# 0_1.net
KiCad netlist of a schematic drawn in EAGLE
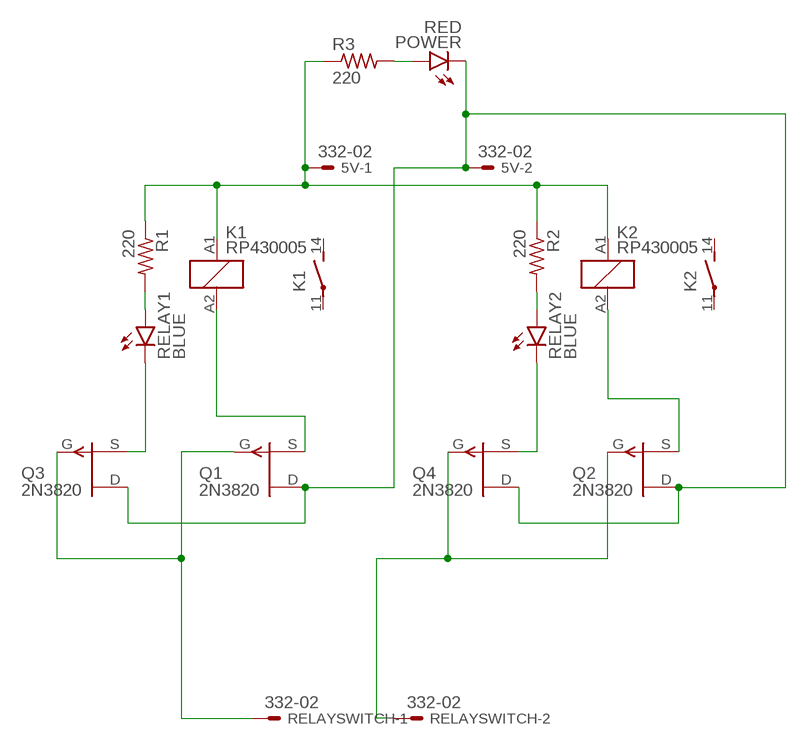
[diagram p0: schematic, sheet 1]

(export (version "E")
  (design (tool "Eeschema 10.0.6"))
  (components
    (comp (ref "5V")
      (value "332-02")
      (footprint "eagle-import:332-02")
      (libsource (lib "eagle-import") (part "332-02"))
    )
    (comp (ref "K1")
      (value "RP430005")
      (footprint "eagle-import:RT-N_O12A5")
      (libsource (lib "eagle-import") (part "RP?304005"))
    )
    (comp (ref "K2")
      (value "RP430005")
      (footprint "eagle-import:RT-N_O12A5")
      (libsource (lib "eagle-import") (part "RP?304005"))
    )
    (comp (ref "POWER")
      (value "RED")
      (footprint "eagle-import:LED5MM")
      (libsource (lib "eagle-import") (part "LED5MM"))
    )
    (comp (ref "Q1")
      (value "2N3820")
      (footprint "eagle-import:TO92")
      (libsource (lib "eagle-import") (part "2N3820"))
    )
    (comp (ref "Q2")
      (value "2N3820")
      (footprint "eagle-import:TO92")
      (libsource (lib "eagle-import") (part "2N3820"))
    )
    (comp (ref "Q3")
      (value "2N3820")
      (footprint "eagle-import:TO92")
      (libsource (lib "eagle-import") (part "2N3820"))
    )
    (comp (ref "Q4")
      (value "2N3820")
      (footprint "eagle-import:TO92")
      (libsource (lib "eagle-import") (part "2N3820"))
    )
    (comp (ref "R1")
      (value "220")
      (footprint "eagle-import:0204_7")
      (libsource (lib "eagle-import") (part "R-US_0204/7"))
    )
    (comp (ref "R2")
      (value "220")
      (footprint "eagle-import:0204_7")
      (libsource (lib "eagle-import") (part "R-US_0204/7"))
    )
    (comp (ref "R3")
      (value "220")
      (footprint "eagle-import:0204_7")
      (libsource (lib "eagle-import") (part "R-US_0204/7"))
    )
    (comp (ref "RELAY1")
      (value "BLUE")
      (footprint "eagle-import:LED5MM")
      (libsource (lib "eagle-import") (part "LED5MM"))
    )
    (comp (ref "RELAY2")
      (value "BLUE")
      (footprint "eagle-import:LED5MM")
      (libsource (lib "eagle-import") (part "LED5MM"))
    )
    (comp (ref "RELAYSWITCH")
      (value "332-02")
      (footprint "eagle-import:332-02")
      (libsource (lib "eagle-import") (part "332-02"))
    )
  )
  (nets
    (net (code "1") (name "Net-(5VA-S)") (class "Default")
      (node (ref "5V") (pin "1") (pinfunction "S_1") (pintype "passive"))
      (node (ref "K1") (pin "A1") (pinfunction "1_A1") (pintype "passive"))
      (node (ref "K2") (pin "A1") (pinfunction "1_A1") (pintype "passive"))
      (node (ref "R1") (pin "1") (pinfunction "1_1") (pintype "passive"))
      (node (ref "R2") (pin "1") (pinfunction "1_1") (pintype "passive"))
      (node (ref "R3") (pin "1") (pinfunction "1_1") (pintype "passive"))
    )
    (net (code "2") (name "Net-(5VB-S)") (class "Default")
      (node (ref "5V") (pin "2") (pinfunction "S_2") (pintype "passive"))
      (node (ref "POWER") (pin "K") (pinfunction "C_K") (pintype "passive"))
      (node (ref "Q1") (pin "3") (pinfunction "D_3") (pintype "passive"))
      (node (ref "Q2") (pin "3") (pinfunction "D_3") (pintype "passive"))
      (node (ref "Q3") (pin "3") (pinfunction "D_3") (pintype "passive"))
      (node (ref "Q4") (pin "3") (pinfunction "D_3") (pintype "passive"))
    )
    (net (code "3") (name "Net-(K1A-2)") (class "Default")
      (node (ref "K1") (pin "A2") (pinfunction "2_A2") (pintype "passive"))
      (node (ref "Q1") (pin "1") (pinfunction "S_1") (pintype "passive"))
    )
    (net (code "4") (name "Net-(K2A-2)") (class "Default")
      (node (ref "K2") (pin "A2") (pinfunction "2_A2") (pintype "passive"))
      (node (ref "Q2") (pin "1") (pinfunction "S_1") (pintype "passive"))
    )
    (net (code "5") (name "Net-(POWER-PadA)") (class "Default")
      (node (ref "POWER") (pin "A") (pinfunction "A_A") (pintype "passive"))
      (node (ref "R3") (pin "2") (pinfunction "2_2") (pintype "passive"))
    )
    (net (code "6") (name "Net-(Q1-G)") (class "Default")
      (node (ref "Q1") (pin "2") (pinfunction "G_2") (pintype "passive"))
      (node (ref "Q3") (pin "2") (pinfunction "G_2") (pintype "passive"))
      (node (ref "RELAYSWITCH") (pin "1") (pinfunction "S_1") (pintype "passive"))
    )
    (net (code "7") (name "Net-(Q2-G)") (class "Default")
      (node (ref "Q2") (pin "2") (pinfunction "G_2") (pintype "passive"))
      (node (ref "Q4") (pin "2") (pinfunction "G_2") (pintype "passive"))
      (node (ref "RELAYSWITCH") (pin "2") (pinfunction "S_2") (pintype "passive"))
    )
    (net (code "8") (name "Net-(Q3-S)") (class "Default")
      (node (ref "Q3") (pin "1") (pinfunction "S_1") (pintype "passive"))
      (node (ref "RELAY1") (pin "K") (pinfunction "C_K") (pintype "passive"))
    )
    (net (code "9") (name "Net-(Q4-S)") (class "Default")
      (node (ref "Q4") (pin "1") (pinfunction "S_1") (pintype "passive"))
      (node (ref "RELAY2") (pin "K") (pinfunction "C_K") (pintype "passive"))
    )
    (net (code "10") (name "Net-(R1-Pad2)") (class "Default")
      (node (ref "R1") (pin "2") (pinfunction "2_2") (pintype "passive"))
      (node (ref "RELAY1") (pin "A") (pinfunction "A_A") (pintype "passive"))
    )
    (net (code "11") (name "Net-(R2-Pad2)") (class "Default")
      (node (ref "R2") (pin "2") (pinfunction "2_2") (pintype "passive"))
      (node (ref "RELAY2") (pin "A") (pinfunction "A_A") (pintype "passive"))
    )
    (net (code "12") (name "unconnected-(K1B-P-Pad11)") (class "Default")
      (node (ref "K1") (pin "11") (pinfunction "P_11") (pintype "passive"))
    )
    (net (code "13") (name "unconnected-(K1B-S-Pad14)") (class "Default")
      (node (ref "K1") (pin "14") (pinfunction "S_14") (pintype "passive"))
    )
    (net (code "14") (name "unconnected-(K2B-P-Pad11)") (class "Default")
      (node (ref "K2") (pin "11") (pinfunction "P_11") (pintype "passive"))
    )
    (net (code "15") (name "unconnected-(K2B-S-Pad14)") (class "Default")
      (node (ref "K2") (pin "14") (pinfunction "S_14") (pintype "passive"))
    )
  )
)
